# PCB_Botny.net
KiCad netlist of a schematic drawn in Altium Designer
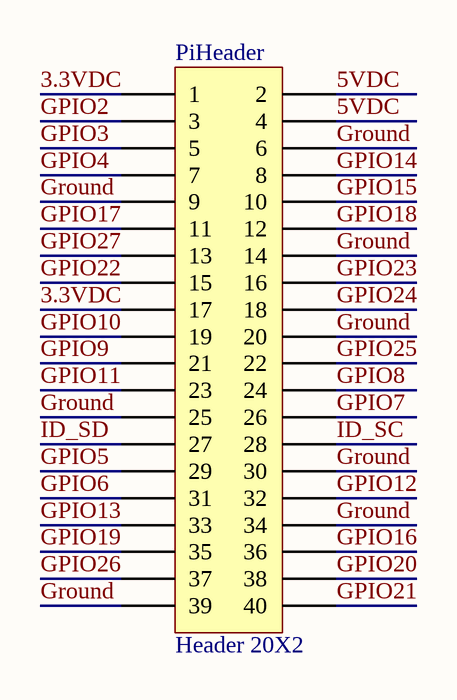
[diagram p0: PCB_Botny.SchDoc]

(export (version "E")
  (design (tool "Eeschema 10.0.6"))
  (components
    (comp (ref "PiHeader")
      (value "Header 20X2")
      (footprint "HDR2X20")
      (description "Header, 20-Pin, Dual row")
      (fields (field (name "PUBLISHER") "Altium Limited"))
      (libsource (lib "Miscellaneous Connectors") (part "Header 20X2"))
    )
  )
  (nets
    (net (code "1") (name "/3.3VDC") (class "Default")
      (node (ref "PiHeader") (pin "1") (pinfunction "1_1") (pintype "passive"))
      (node (ref "PiHeader") (pin "17") (pinfunction "17_17") (pintype "passive"))
    )
    (net (code "2") (name "/5VDC") (class "Default")
      (node (ref "PiHeader") (pin "2") (pinfunction "2_2") (pintype "passive"))
      (node (ref "PiHeader") (pin "4") (pinfunction "4_4") (pintype "passive"))
    )
    (net (code "3") (name "/GPIO2") (class "Default")
      (node (ref "PiHeader") (pin "3") (pinfunction "3_3") (pintype "passive"))
    )
    (net (code "4") (name "/GPIO3") (class "Default")
      (node (ref "PiHeader") (pin "5") (pinfunction "5_5") (pintype "passive"))
    )
    (net (code "5") (name "/GPIO4") (class "Default")
      (node (ref "PiHeader") (pin "7") (pinfunction "7_7") (pintype "passive"))
    )
    (net (code "6") (name "/GPIO5") (class "Default")
      (node (ref "PiHeader") (pin "29") (pinfunction "29_29") (pintype "passive"))
    )
    (net (code "7") (name "/GPIO6") (class "Default")
      (node (ref "PiHeader") (pin "31") (pinfunction "31_31") (pintype "passive"))
    )
    (net (code "8") (name "/GPIO7") (class "Default")
      (node (ref "PiHeader") (pin "26") (pinfunction "26_26") (pintype "passive"))
    )
    (net (code "9") (name "/GPIO8") (class "Default")
      (node (ref "PiHeader") (pin "24") (pinfunction "24_24") (pintype "passive"))
    )
    (net (code "10") (name "/GPIO9") (class "Default")
      (node (ref "PiHeader") (pin "21") (pinfunction "21_21") (pintype "passive"))
    )
    (net (code "11") (name "/GPIO10") (class "Default")
      (node (ref "PiHeader") (pin "19") (pinfunction "19_19") (pintype "passive"))
    )
    (net (code "12") (name "/GPIO11") (class "Default")
      (node (ref "PiHeader") (pin "23") (pinfunction "23_23") (pintype "passive"))
    )
    (net (code "13") (name "/GPIO12") (class "Default")
      (node (ref "PiHeader") (pin "32") (pinfunction "32_32") (pintype "passive"))
    )
    (net (code "14") (name "/GPIO13") (class "Default")
      (node (ref "PiHeader") (pin "33") (pinfunction "33_33") (pintype "passive"))
    )
    (net (code "15") (name "/GPIO14") (class "Default")
      (node (ref "PiHeader") (pin "8") (pinfunction "8_8") (pintype "passive"))
    )
    (net (code "16") (name "/GPIO15") (class "Default")
      (node (ref "PiHeader") (pin "10") (pinfunction "10_10") (pintype "passive"))
    )
    (net (code "17") (name "/GPIO16") (class "Default")
      (node (ref "PiHeader") (pin "36") (pinfunction "36_36") (pintype "passive"))
    )
    (net (code "18") (name "/GPIO17") (class "Default")
      (node (ref "PiHeader") (pin "11") (pinfunction "11_11") (pintype "passive"))
    )
    (net (code "19") (name "/GPIO18") (class "Default")
      (node (ref "PiHeader") (pin "12") (pinfunction "12_12") (pintype "passive"))
    )
    (net (code "20") (name "/GPIO19") (class "Default")
      (node (ref "PiHeader") (pin "35") (pinfunction "35_35") (pintype "passive"))
    )
    (net (code "21") (name "/GPIO20") (class "Default")
      (node (ref "PiHeader") (pin "38") (pinfunction "38_38") (pintype "passive"))
    )
    (net (code "22") (name "/GPIO21") (class "Default")
      (node (ref "PiHeader") (pin "40") (pinfunction "40_40") (pintype "passive"))
    )
    (net (code "23") (name "/GPIO22") (class "Default")
      (node (ref "PiHeader") (pin "15") (pinfunction "15_15") (pintype "passive"))
    )
    (net (code "24") (name "/GPIO23") (class "Default")
      (node (ref "PiHeader") (pin "16") (pinfunction "16_16") (pintype "passive"))
    )
    (net (code "25") (name "/GPIO24") (class "Default")
      (node (ref "PiHeader") (pin "18") (pinfunction "18_18") (pintype "passive"))
    )
    (net (code "26") (name "/GPIO25") (class "Default")
      (node (ref "PiHeader") (pin "22") (pinfunction "22_22") (pintype "passive"))
    )
    (net (code "27") (name "/GPIO26") (class "Default")
      (node (ref "PiHeader") (pin "37") (pinfunction "37_37") (pintype "passive"))
    )
    (net (code "28") (name "/GPIO27") (class "Default")
      (node (ref "PiHeader") (pin "13") (pinfunction "13_13") (pintype "passive"))
    )
    (net (code "29") (name "/Ground") (class "Default")
      (node (ref "PiHeader") (pin "14") (pinfunction "14_14") (pintype "passive"))
      (node (ref "PiHeader") (pin "20") (pinfunction "20_20") (pintype "passive"))
      (node (ref "PiHeader") (pin "25") (pinfunction "25_25") (pintype "passive"))
      (node (ref "PiHeader") (pin "30") (pinfunction "30_30") (pintype "passive"))
      (node (ref "PiHeader") (pin "34") (pinfunction "34_34") (pintype "passive"))
      (node (ref "PiHeader") (pin "39") (pinfunction "39_39") (pintype "passive"))
      (node (ref "PiHeader") (pin "6") (pinfunction "6_6") (pintype "passive"))
      (node (ref "PiHeader") (pin "9") (pinfunction "9_9") (pintype "passive"))
    )
    (net (code "30") (name "/ID_SC") (class "Default")
      (node (ref "PiHeader") (pin "28") (pinfunction "28_28") (pintype "passive"))
    )
    (net (code "31") (name "/ID_SD") (class "Default")
      (node (ref "PiHeader") (pin "27") (pinfunction "27_27") (pintype "passive"))
    )
  )
)
